# Konnektduino_knx_Rev_1_0.net
KiCad netlist of a schematic drawn in EAGLE
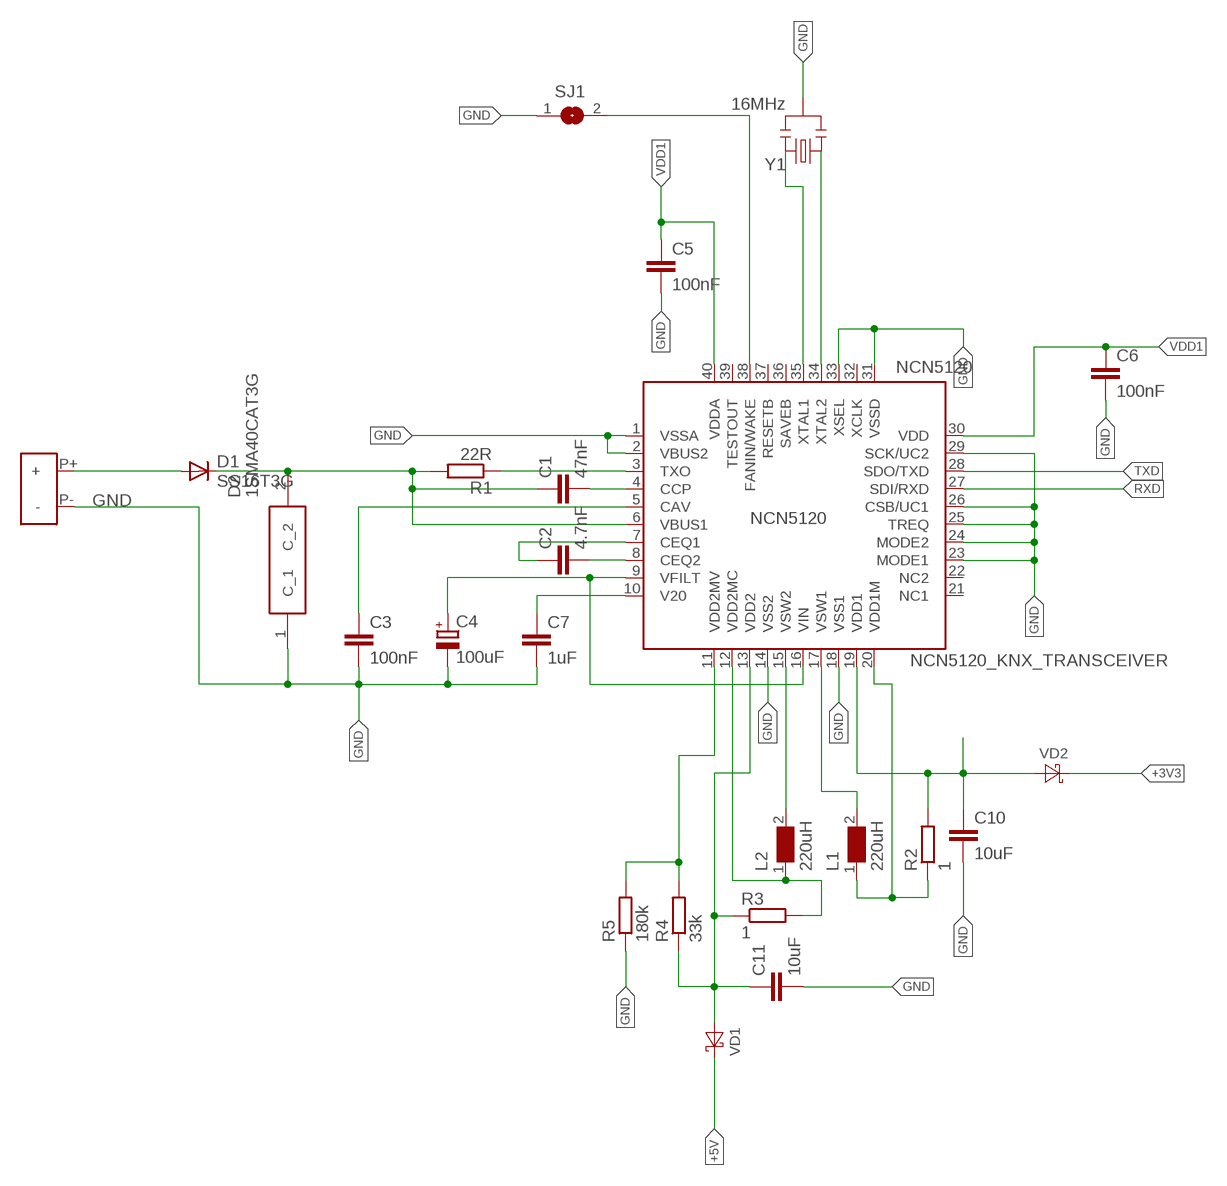
[diagram p0: schematic, sheet 1]

(export (version "E")
  (design (tool "Eeschema 10.0.6"))
  (components
    (comp (ref "C1")
      (value "47nF")
      (footprint "eagle-import:C0603")
      (libsource (lib "eagle-import") (part "C-EUC0603"))
    )
    (comp (ref "C2")
      (value "4.7nF")
      (footprint "eagle-import:C0603")
      (libsource (lib "eagle-import") (part "C-EUC0603"))
    )
    (comp (ref "C3")
      (value "100nF")
      (footprint "eagle-import:C0603")
      (libsource (lib "eagle-import") (part "C-EUC0603"))
    )
    (comp (ref "C4")
      (value "100uF")
      (footprint "eagle-import:PANASONIC_E")
      (libsource (lib "eagle-import") (part "CPOL-EUE"))
    )
    (comp (ref "C5")
      (value "100nF")
      (footprint "eagle-import:C0603")
      (libsource (lib "eagle-import") (part "C-EUC0603"))
    )
    (comp (ref "C6")
      (value "100nF")
      (footprint "eagle-import:C0603")
      (libsource (lib "eagle-import") (part "C-EUC0603"))
    )
    (comp (ref "C7")
      (value "1uF")
      (footprint "eagle-import:C0603")
      (libsource (lib "eagle-import") (part "C-EUC0603"))
    )
    (comp (ref "C10")
      (value "10uF")
      (footprint "eagle-import:C0603")
      (libsource (lib "eagle-import") (part "C-EUC0603"))
    )
    (comp (ref "C11")
      (value "10uF")
      (footprint "eagle-import:C0603")
      (libsource (lib "eagle-import") (part "C-EUC0603"))
    )
    (comp (ref "D1")
      (value "SS16T3G")
      (footprint "eagle-import:SMA-DIODE_ALT")
      (libsource (lib "eagle-import") (part "DIODESMA-ALT"))
    )
    (comp (ref "D2")
      (value "1SMA40CAT3G")
      (footprint "eagle-import:DIONM5226X220N")
      (fields (field (name "RS_PART_NUMBER") "8008942P"))
      (libsource (lib "eagle-import") (part "1SMA40CAT3G"))
    )
    (comp (ref "L1")
      (value "220uH")
      (footprint "eagle-import:WE-PD2_7850")
      (libsource (lib "eagle-import") (part "WE-PD2_7850"))
    )
    (comp (ref "L2")
      (value "220uH")
      (footprint "eagle-import:WE-PD2_7850")
      (libsource (lib "eagle-import") (part "WE-PD2_7850"))
    )
    (comp (ref "NCN5120")
      (value "NCN5120_KNX_TRANSCEIVER")
      (footprint "eagle-import:QFN40")
      (libsource (lib "eagle-import") (part "NCN5120_KNX_TRANSCEIVER"))
    )
    (comp (ref "R1")
      (value "22R")
      (footprint "eagle-import:R1218")
      (libsource (lib "eagle-import") (part "R-EU_R1218"))
    )
    (comp (ref "R2")
      (value "1")
      (footprint "eagle-import:R0603")
      (libsource (lib "eagle-import") (part "R-EU_R0603"))
    )
    (comp (ref "R3")
      (value "1")
      (footprint "eagle-import:R0603")
      (libsource (lib "eagle-import") (part "R-EU_R0603"))
    )
    (comp (ref "R4")
      (value "33k")
      (footprint "eagle-import:R0603")
      (libsource (lib "eagle-import") (part "R-EU_R0603"))
    )
    (comp (ref "R5")
      (value "180k")
      (footprint "eagle-import:R0603")
      (libsource (lib "eagle-import") (part "R-EU_R0603"))
    )
    (comp (ref "SJ1")
      (value "SJW")
      (footprint "eagle-import:SJW")
      (libsource (lib "eagle-import") (part "SJW"))
    )
    (comp (ref "U$2")
      (value "KNX_KLEMME")
      (footprint "eagle-import:KNX_KLEMME")
      (libsource (lib "eagle-import") (part "KNX_KLEMME"))
    )
    (comp (ref "VD1")
      (value "DIODE-SCHOTTKY-0603")
      (footprint "eagle-import:D0603")
      (libsource (lib "eagle-import") (part "DIODE-SCHOTTKY-0603"))
    )
    (comp (ref "VD2")
      (value "DIODE-SCHOTTKY-0603")
      (footprint "eagle-import:D0603")
      (libsource (lib "eagle-import") (part "DIODE-SCHOTTKY-0603"))
    )
    (comp (ref "Y1")
      (value "16MHz")
      (footprint "eagle-import:RESONATOR-SMD")
      (libsource (lib "eagle-import") (part "RESONATORSMD"))
    )
  )
  (nets
    (net (code "1") (name "+3V3") (class "Default")
      (node (ref "VD2") (pin "C") (pinfunction "C_C") (pintype "passive"))
    )
    (net (code "2") (name "+5V") (class "Default")
      (node (ref "VD1") (pin "C") (pinfunction "C_C") (pintype "passive"))
    )
    (net (code "3") (name "GND") (class "Default")
      (node (ref "C10") (pin "2") (pinfunction "2_2") (pintype "passive"))
      (node (ref "C11") (pin "2") (pinfunction "2_2") (pintype "passive"))
      (node (ref "C3") (pin "2") (pinfunction "2_2") (pintype "passive"))
      (node (ref "C4") (pin "-") (pinfunction "-_-") (pintype "passive"))
      (node (ref "C5") (pin "2") (pinfunction "2_2") (pintype "passive"))
      (node (ref "C6") (pin "2") (pinfunction "2_2") (pintype "passive"))
      (node (ref "C7") (pin "2") (pinfunction "2_2") (pintype "passive"))
      (node (ref "D2") (pin "1") (pinfunction "C_1_1") (pintype "bidirectional"))
      (node (ref "NCN5120") (pin "1") (pinfunction "VSSA_1") (pintype "bidirectional"))
      (node (ref "NCN5120") (pin "14") (pinfunction "VSS2_14") (pintype "bidirectional"))
      (node (ref "NCN5120") (pin "18") (pinfunction "VSS1_18") (pintype "bidirectional"))
      (node (ref "NCN5120") (pin "2") (pinfunction "VBUS2_2") (pintype "bidirectional"))
      (node (ref "NCN5120") (pin "23") (pinfunction "MODE1_23") (pintype "bidirectional"))
      (node (ref "NCN5120") (pin "24") (pinfunction "MODE2_24") (pintype "bidirectional"))
      (node (ref "NCN5120") (pin "25") (pinfunction "TREQ_25") (pintype "bidirectional"))
      (node (ref "NCN5120") (pin "26") (pinfunction "CSB/UC1_26") (pintype "bidirectional"))
      (node (ref "NCN5120") (pin "29") (pinfunction "SCK/UC2_29") (pintype "bidirectional"))
      (node (ref "NCN5120") (pin "31") (pinfunction "VSSD_31") (pintype "bidirectional"))
      (node (ref "NCN5120") (pin "33") (pinfunction "XSEL_33") (pintype "bidirectional"))
      (node (ref "R5") (pin "1") (pinfunction "1_1") (pintype "passive"))
      (node (ref "SJ1") (pin "1") (pinfunction "1_1") (pintype "passive"))
      (node (ref "U$2") (pin "P-") (pinfunction "-_P-") (pintype "bidirectional"))
      (node (ref "Y1") (pin "2") (pinfunction "2_2") (pintype "passive"))
    )
    (net (code "4") (name "Net-(D2-C_2)") (class "Default")
      (node (ref "C1") (pin "1") (pinfunction "1_1") (pintype "passive"))
      (node (ref "D1") (pin "C") (pinfunction "C_C") (pintype "passive"))
      (node (ref "D2") (pin "2") (pinfunction "C_2_2") (pintype "bidirectional"))
      (node (ref "NCN5120") (pin "6") (pinfunction "VBUS1_6") (pintype "bidirectional"))
      (node (ref "R1") (pin "2") (pinfunction "2_2") (pintype "passive"))
    )
    (net (code "5") (name "Net-(NCN5120-CAV)") (class "Default")
      (node (ref "C3") (pin "1") (pinfunction "1_1") (pintype "passive"))
      (node (ref "NCN5120") (pin "5") (pinfunction "CAV_5") (pintype "bidirectional"))
    )
    (net (code "6") (name "Net-(NCN5120-CCP)") (class "Default")
      (node (ref "C1") (pin "2") (pinfunction "2_2") (pintype "passive"))
      (node (ref "NCN5120") (pin "4") (pinfunction "CCP_4") (pintype "bidirectional"))
    )
    (net (code "7") (name "Net-(NCN5120-CEQ1)") (class "Default")
      (node (ref "C2") (pin "1") (pinfunction "1_1") (pintype "passive"))
      (node (ref "NCN5120") (pin "7") (pinfunction "CEQ1_7") (pintype "bidirectional"))
    )
    (net (code "8") (name "Net-(NCN5120-CEQ2)") (class "Default")
      (node (ref "C2") (pin "2") (pinfunction "2_2") (pintype "passive"))
      (node (ref "NCN5120") (pin "8") (pinfunction "CEQ2_8") (pintype "bidirectional"))
    )
    (net (code "9") (name "Net-(NCN5120-FANIN{slash}WAKE)") (class "Default")
      (node (ref "NCN5120") (pin "38") (pinfunction "FANIN/WAKE_38") (pintype "bidirectional"))
      (node (ref "SJ1") (pin "2") (pinfunction "2_2") (pintype "passive"))
    )
    (net (code "10") (name "Net-(NCN5120-TXO)") (class "Default")
      (node (ref "NCN5120") (pin "3") (pinfunction "TXO_3") (pintype "bidirectional"))
      (node (ref "R1") (pin "1") (pinfunction "1_1") (pintype "passive"))
    )
    (net (code "11") (name "Net-(NCN5120-V20)") (class "Default")
      (node (ref "C7") (pin "1") (pinfunction "1_1") (pintype "passive"))
      (node (ref "NCN5120") (pin "10") (pinfunction "V20_10") (pintype "bidirectional"))
    )
    (net (code "12") (name "Net-(NCN5120-VDD1M)") (class "Default")
      (node (ref "L1") (pin "1") (pinfunction "1_1") (pintype "passive"))
      (node (ref "NCN5120") (pin "20") (pinfunction "VDD1M_20") (pintype "bidirectional"))
      (node (ref "R2") (pin "1") (pinfunction "1_1") (pintype "passive"))
    )
    (net (code "13") (name "Net-(NCN5120-VDD2)") (class "Default")
      (node (ref "C11") (pin "1") (pinfunction "1_1") (pintype "passive"))
      (node (ref "NCN5120") (pin "13") (pinfunction "VDD2_13") (pintype "bidirectional"))
      (node (ref "R3") (pin "1") (pinfunction "1_1") (pintype "passive"))
      (node (ref "R4") (pin "1") (pinfunction "1_1") (pintype "passive"))
      (node (ref "VD1") (pin "A") (pinfunction "A_A") (pintype "passive"))
    )
    (net (code "14") (name "Net-(NCN5120-VDD2MC)") (class "Default")
      (node (ref "L2") (pin "1") (pinfunction "1_1") (pintype "passive"))
      (node (ref "NCN5120") (pin "12") (pinfunction "VDD2MC_12") (pintype "bidirectional"))
      (node (ref "R3") (pin "2") (pinfunction "2_2") (pintype "passive"))
    )
    (net (code "15") (name "Net-(NCN5120-VDD2MV)") (class "Default")
      (node (ref "NCN5120") (pin "11") (pinfunction "VDD2MV_11") (pintype "bidirectional"))
      (node (ref "R4") (pin "2") (pinfunction "2_2") (pintype "passive"))
      (node (ref "R5") (pin "2") (pinfunction "2_2") (pintype "passive"))
    )
    (net (code "16") (name "Net-(NCN5120-VFILT)") (class "Default")
      (node (ref "C4") (pin "+") (pinfunction "+_+") (pintype "passive"))
      (node (ref "NCN5120") (pin "16") (pinfunction "VIN_16") (pintype "bidirectional"))
      (node (ref "NCN5120") (pin "9") (pinfunction "VFILT_9") (pintype "bidirectional"))
    )
    (net (code "17") (name "Net-(NCN5120-VSW1)") (class "Default")
      (node (ref "L1") (pin "2") (pinfunction "2_2") (pintype "passive"))
      (node (ref "NCN5120") (pin "17") (pinfunction "VSW1_17") (pintype "bidirectional"))
    )
    (net (code "18") (name "Net-(NCN5120-VSW2)") (class "Default")
      (node (ref "L2") (pin "2") (pinfunction "2_2") (pintype "passive"))
      (node (ref "NCN5120") (pin "15") (pinfunction "VSW2_15") (pintype "bidirectional"))
    )
    (net (code "19") (name "Net-(NCN5120-XTAL1)") (class "Default")
      (node (ref "NCN5120") (pin "35") (pinfunction "XTAL1_35") (pintype "bidirectional"))
      (node (ref "Y1") (pin "3") (pinfunction "3_3") (pintype "passive"))
    )
    (net (code "20") (name "Net-(NCN5120-XTAL2)") (class "Default")
      (node (ref "NCN5120") (pin "34") (pinfunction "XTAL2_34") (pintype "bidirectional"))
      (node (ref "Y1") (pin "1") (pinfunction "1_1") (pintype "passive"))
    )
    (net (code "21") (name "Net-(U$2-+)") (class "Default")
      (node (ref "D1") (pin "A") (pinfunction "A_A") (pintype "passive"))
      (node (ref "U$2") (pin "P+") (pinfunction "+_P+") (pintype "bidirectional"))
    )
    (net (code "22") (name "RXD") (class "Default")
      (node (ref "NCN5120") (pin "27") (pinfunction "SDI/RXD_27") (pintype "bidirectional"))
    )
    (net (code "23") (name "TXD") (class "Default")
      (node (ref "NCN5120") (pin "28") (pinfunction "SDO/TXD_28") (pintype "bidirectional"))
    )
    (net (code "24") (name "VDD1") (class "Default")
      (node (ref "C10") (pin "1") (pinfunction "1_1") (pintype "passive"))
      (node (ref "C5") (pin "1") (pinfunction "1_1") (pintype "passive"))
      (node (ref "C6") (pin "1") (pinfunction "1_1") (pintype "passive"))
      (node (ref "NCN5120") (pin "19") (pinfunction "VDD1_19") (pintype "bidirectional"))
      (node (ref "NCN5120") (pin "30") (pinfunction "VDD_30") (pintype "bidirectional"))
      (node (ref "NCN5120") (pin "40") (pinfunction "VDDA_40") (pintype "bidirectional"))
      (node (ref "R2") (pin "2") (pinfunction "2_2") (pintype "passive"))
      (node (ref "VD2") (pin "A") (pinfunction "A_A") (pintype "passive"))
    )
    (net (code "25") (name "unconnected-(NCN5120-NC1-Pad21)") (class "Default")
      (node (ref "NCN5120") (pin "21") (pinfunction "NC1_21") (pintype "bidirectional"))
    )
    (net (code "26") (name "unconnected-(NCN5120-NC2-Pad22)") (class "Default")
      (node (ref "NCN5120") (pin "22") (pinfunction "NC2_22") (pintype "bidirectional"))
    )
    (net (code "27") (name "unconnected-(NCN5120-RESETB-Pad37)") (class "Default")
      (node (ref "NCN5120") (pin "37") (pinfunction "RESETB_37") (pintype "bidirectional"))
    )
    (net (code "28") (name "unconnected-(NCN5120-SAVEB-Pad36)") (class "Default")
      (node (ref "NCN5120") (pin "36") (pinfunction "SAVEB_36") (pintype "bidirectional"))
    )
    (net (code "29") (name "unconnected-(NCN5120-TESTOUT-Pad39)") (class "Default")
      (node (ref "NCN5120") (pin "39") (pinfunction "TESTOUT_39") (pintype "bidirectional"))
    )
    (net (code "30") (name "unconnected-(NCN5120-XCLK-Pad32)") (class "Default")
      (node (ref "NCN5120") (pin "32") (pinfunction "XCLK_32") (pintype "bidirectional"))
    )
  )
)
